# Payloadv03.net
KiCad netlist of a schematic drawn in EAGLE
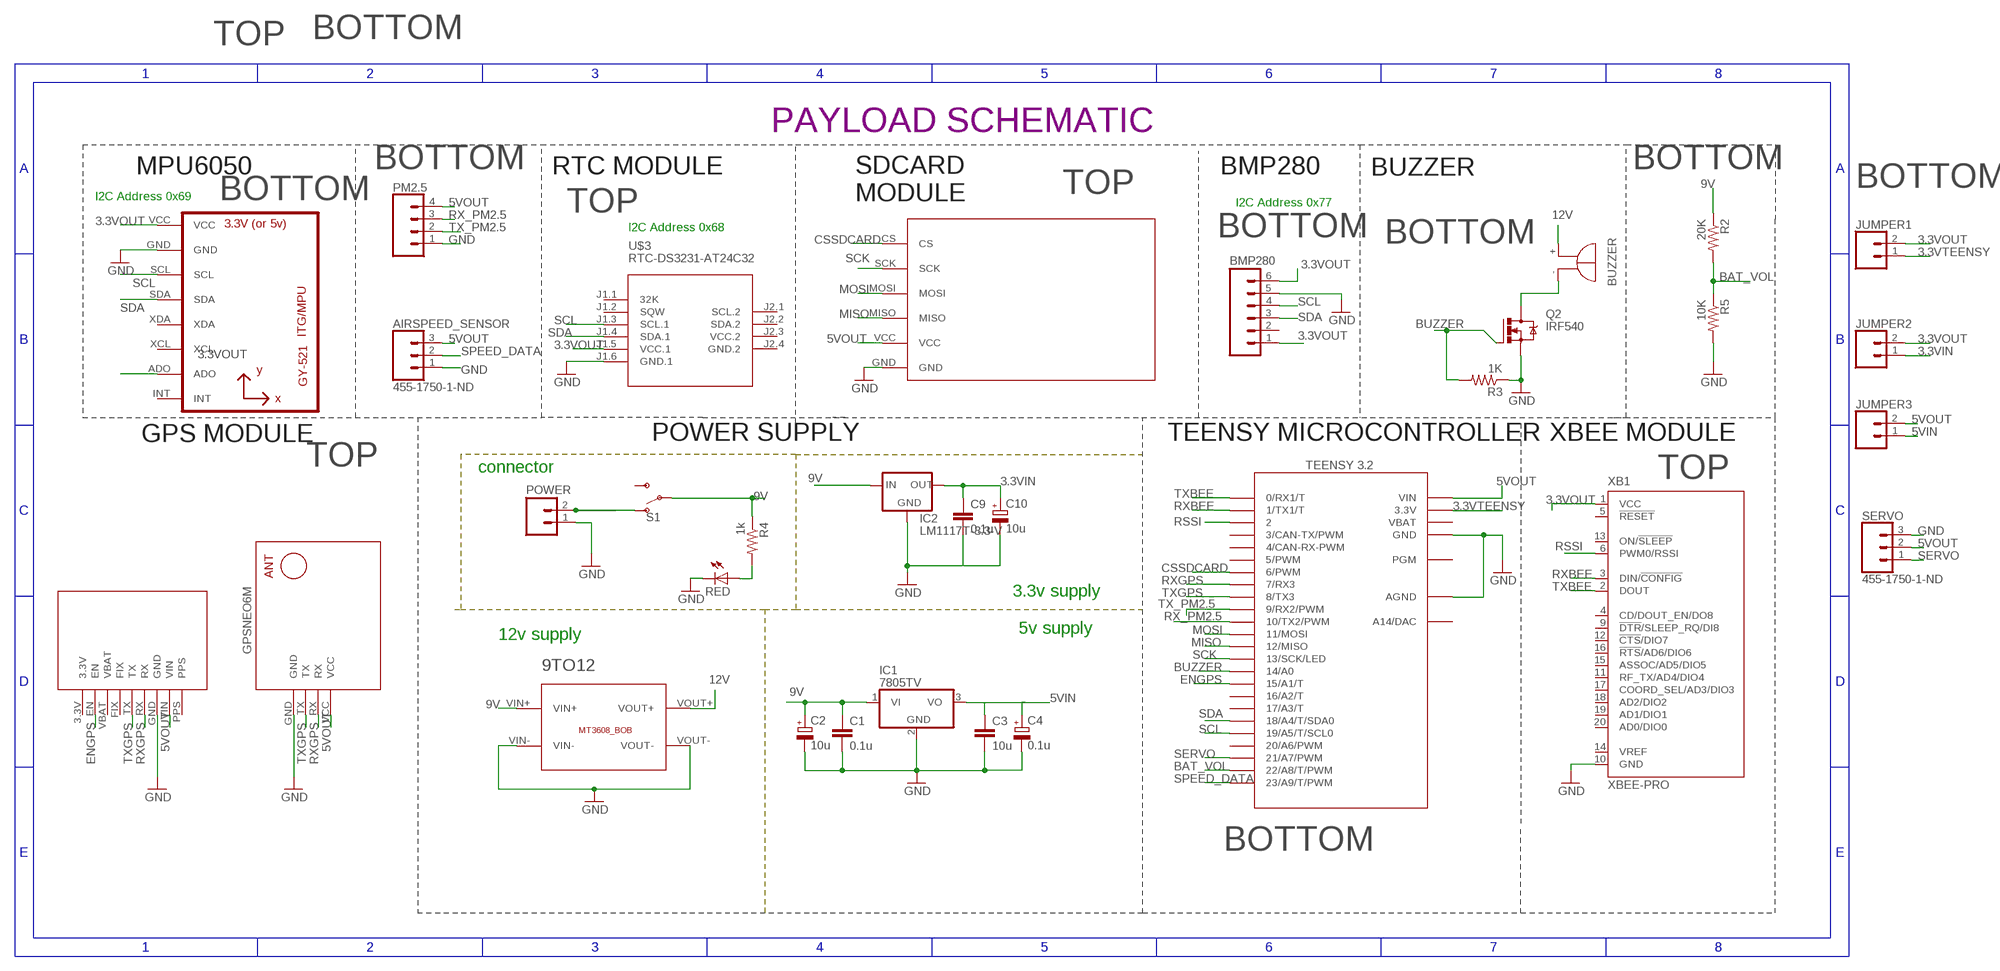
[diagram p0: schematic, sheet 1]

(export (version "E")
  (design (tool "Eeschema 10.0.6"))
  (components
    (comp (ref "9TO12")
      (value "BREAKOUTS_MT3608_BOB")
      (footprint "eagle-import:BREAKOUTS_MT3608_BOB")
      (libsource (lib "eagle-import") (part "BREAKOUTS_MT3608_BOB"))
    )
    (comp (ref "AIRSPEED_SENSOR")
      (value "455-1750-1-ND")
      (footprint "eagle-import:1X03")
      (libsource (lib "eagle-import") (part "CONN_03"))
    )
    (comp (ref "BMP280")
      (value "M06")
      (footprint "eagle-import:06P")
      (libsource (lib "eagle-import") (part "M06"))
    )
    (comp (ref "C1")
      (value "0.1u")
      (footprint "eagle-import:C025-025X050")
      (libsource (lib "eagle-import") (part "C-EU025-025X050"))
    )
    (comp (ref "C2")
      (value "10u")
      (footprint "eagle-import:E2,5-6")
      (libsource (lib "eagle-import") (part "CPOL-EUE2.5-6"))
    )
    (comp (ref "C3")
      (value "10u")
      (footprint "eagle-import:C025-025X050")
      (libsource (lib "eagle-import") (part "C-EU025-025X050"))
    )
    (comp (ref "C4")
      (value "0.1u")
      (footprint "eagle-import:E2,5-6")
      (libsource (lib "eagle-import") (part "CPOL-EUE2.5-6"))
    )
    (comp (ref "C9")
      (value "0.1u")
      (footprint "eagle-import:C025-025X050")
      (libsource (lib "eagle-import") (part "C-EU025-025X050"))
    )
    (comp (ref "C10")
      (value "10u")
      (footprint "eagle-import:E2,5-6")
      (libsource (lib "eagle-import") (part "CPOL-EUE2.5-6"))
    )
    (comp (ref "IC1")
      (value "7805TV")
      (footprint "eagle-import:TO220V")
      (libsource (lib "eagle-import") (part "78TV05"))
    )
    (comp (ref "IC2")
      (value "LM1117T-3.3-V")
      (footprint "eagle-import:TO220V")
      (libsource (lib "eagle-import") (part "LM1117T--V3.3"))
    )
    (comp (ref "JUMPER1")
      (value "CONN_02")
      (footprint "eagle-import:1X02")
      (libsource (lib "eagle-import") (part "CONN_02"))
    )
    (comp (ref "JUMPER2")
      (value "CONN_02")
      (footprint "eagle-import:1X02")
      (libsource (lib "eagle-import") (part "CONN_02"))
    )
    (comp (ref "JUMPER3")
      (value "CONN_02")
      (footprint "eagle-import:1X02")
      (libsource (lib "eagle-import") (part "CONN_02"))
    )
    (comp (ref "PM2.5")
      (value "CONN_04")
      (footprint "eagle-import:1X04")
      (libsource (lib "eagle-import") (part "CONN_04"))
    )
    (comp (ref "POWER")
      (value "CEDT_JANUARY_2015_V5_M02")
      (footprint "eagle-import:CEDT_JANUARY_2015_V5_02P")
      (libsource (lib "eagle-import") (part "CEDT_JANUARY_2015_V5_M02"))
    )
    (comp (ref "Q2")
      (value "IRF540")
      (footprint "eagle-import:TO220BV")
      (libsource (lib "eagle-import") (part "IRF540"))
    )
    (comp (ref "R2")
      (value "20K")
      (footprint "eagle-import:0204_7")
      (libsource (lib "eagle-import") (part "R-US_0204/7"))
    )
    (comp (ref "R3")
      (value "1K")
      (footprint "eagle-import:0204_7")
      (libsource (lib "eagle-import") (part "R-US_0204/7"))
    )
    (comp (ref "R4")
      (value "1k")
      (footprint "eagle-import:0204_7")
      (libsource (lib "eagle-import") (part "R-US_0204/7"))
    )
    (comp (ref "R5")
      (value "10K")
      (footprint "eagle-import:0204_7")
      (libsource (lib "eagle-import") (part "R-US_0204/7"))
    )
    (comp (ref "RED")
      (value "red")
      (footprint "eagle-import:LED3MM")
      (libsource (lib "eagle-import") (part "LED3MM"))
    )
    (comp (ref "S1")
      (value "SWITCH-SPDT-PTH-11.6X4.0MM")
      (footprint "eagle-import:SWITCH_SPDT_PTH_11.6X4.0MM")
      (libsource (lib "eagle-import") (part "SWITCH-SPDT-PTH-11.6X4.0MM"))
    )
    (comp (ref "SERVO")
      (value "455-1750-1-ND")
      (footprint "eagle-import:1X03")
      (libsource (lib "eagle-import") (part "CONN_03"))
    )
    (comp (ref "SG1")
      (value "BUZZER_EB2209A")
      (footprint "eagle-import:BUZZER_EB2209A")
      (libsource (lib "eagle-import") (part "BUZZER_EB2209A"))
    )
    (comp (ref "U$1")
      (value "GPS-RECEIVER-NEO6M")
      (footprint "eagle-import:GPS-RECEIVER-NEO6M")
      (libsource (lib "eagle-import") (part "GPS-RECEIVER-NEO6M"))
    )
    (comp (ref "U$2")
      (value "TEENSY_3.1-3.2_OUTER_ROW")
      (footprint "eagle-import:TEENSY_3.0-3.2&LC_OUTER_ROW")
      (libsource (lib "eagle-import") (part "TEENSY_3.1-3.2_OUTER_ROW"))
    )
    (comp (ref "U$3")
      (value "RTC-DS3231-AT24C32")
      (footprint "eagle-import:RTC-DS3231-AT24C32")
      (libsource (lib "eagle-import") (part "RTC-DS3231-AT24C32"))
    )
    (comp (ref "U$4")
      (value "ADAFRUIT_GPS")
      (footprint "eagle-import:ADAFRUIT_GPS")
      (libsource (lib "eagle-import") (part "ADAFRUIT_GPS"))
    )
    (comp (ref "U$5")
      (value "SDCARD")
      (footprint "eagle-import:M0SDCARDMODULE")
      (libsource (lib "eagle-import") (part "SDCARD"))
    )
    (comp (ref "U1")
      (value "GY-521MPU6050")
      (footprint "eagle-import:GY-521")
      (libsource (lib "eagle-import") (part "GY-521MPU6050"))
    )
    (comp (ref "XB1")
      (value "XBEE-PRO")
      (footprint "eagle-import:XBEE-PRO")
      (fields (field (name "MPN") "XBP24-AWI-001"))
      (libsource (lib "eagle-import") (part "XBEE-PRO"))
    )
  )
  (nets
    (net (code "1") (name "/3.3VIN") (class "Default")
      (node (ref "C10") (pin "+") (pinfunction "+_+") (pintype "passive"))
      (node (ref "C9") (pin "1") (pinfunction "1_1") (pintype "passive"))
      (node (ref "IC2") (pin "2") (pinfunction "OUT_2") (pintype "passive"))
      (node (ref "JUMPER2") (pin "1") (pinfunction "1_1") (pintype "passive"))
    )
    (net (code "2") (name "/3.3VOUT") (class "Default")
      (node (ref "BMP280") (pin "1") (pinfunction "1_1") (pintype "passive"))
      (node (ref "BMP280") (pin "6") (pinfunction "6_6") (pintype "passive"))
      (node (ref "JUMPER1") (pin "2") (pinfunction "2_2") (pintype "passive"))
      (node (ref "JUMPER2") (pin "2") (pinfunction "2_2") (pintype "passive"))
      (node (ref "U$3") (pin "J1.5") (pinfunction "VCC.1_J1.5") (pintype "power_in"))
      (node (ref "U1") (pin "ADO") (pinfunction "ADO_ADO") (pintype "bidirectional"))
      (node (ref "U1") (pin "VCC") (pinfunction "VCC_VCC") (pintype "bidirectional"))
      (node (ref "XB1") (pin "1") (pinfunction "VCC_1") (pintype "power_in"))
    )
    (net (code "3") (name "/3.3VTEENSY") (class "Default")
      (node (ref "JUMPER1") (pin "1") (pinfunction "1_1") (pintype "passive"))
      (node (ref "U$2") (pin "3.3V") (pinfunction "3.3V_3.3V") (pintype "power_in"))
      (node (ref "U$2") (pin "3.3V1") (pinfunction "3.3V_3.3V1") (pintype "power_in"))
    )
    (net (code "4") (name "/5VIN") (class "Default")
      (node (ref "C3") (pin "1") (pinfunction "1_1") (pintype "passive"))
      (node (ref "C4") (pin "+") (pinfunction "+_+") (pintype "passive"))
      (node (ref "IC1") (pin "3") (pinfunction "VO_3") (pintype "passive"))
      (node (ref "JUMPER3") (pin "1") (pinfunction "1_1") (pintype "passive"))
    )
    (net (code "5") (name "/5VOUT") (class "Default")
      (node (ref "AIRSPEED_SENSOR") (pin "3") (pinfunction "3_3") (pintype "passive"))
      (node (ref "JUMPER3") (pin "2") (pinfunction "2_2") (pintype "passive"))
      (node (ref "PM2.5") (pin "4") (pinfunction "4_4") (pintype "passive"))
      (node (ref "SERVO") (pin "2") (pinfunction "2_2") (pintype "passive"))
      (node (ref "U$1") (pin "VCC") (pinfunction "VCC_VCC") (pintype "power_in"))
      (node (ref "U$2") (pin "VIN") (pinfunction "VIN_VIN") (pintype "power_in"))
      (node (ref "U$4") (pin "VIN") (pinfunction "VIN_VIN") (pintype "bidirectional"))
      (node (ref "U$5") (pin "VCC") (pinfunction "VCC_VCC") (pintype "bidirectional"))
    )
    (net (code "6") (name "/9V") (class "Default")
      (node (ref "9TO12") (pin "VIN+") (pinfunction "VIN+_VIN+") (pintype "bidirectional"))
      (node (ref "C1") (pin "1") (pinfunction "1_1") (pintype "passive"))
      (node (ref "C2") (pin "+") (pinfunction "+_+") (pintype "passive"))
      (node (ref "IC1") (pin "1") (pinfunction "VI_1") (pintype "input"))
      (node (ref "IC2") (pin "3") (pinfunction "IN_3") (pintype "input"))
      (node (ref "R2") (pin "1") (pinfunction "1_1") (pintype "passive"))
      (node (ref "R4") (pin "1") (pinfunction "1_1") (pintype "passive"))
      (node (ref "S1") (pin "2") (pinfunction "P_2") (pintype "passive"))
    )
    (net (code "7") (name "/12V") (class "Default")
      (node (ref "9TO12") (pin "VOUT+") (pinfunction "VOUT+_VOUT+") (pintype "bidirectional"))
      (node (ref "SG1") (pin "+") (pinfunction "+_+") (pintype "passive"))
    )
    (net (code "8") (name "/BAT_VOL") (class "Default")
      (node (ref "R2") (pin "2") (pinfunction "2_2") (pintype "passive"))
      (node (ref "R5") (pin "1") (pinfunction "1_1") (pintype "passive"))
      (node (ref "U$2") (pin "22/A8") (pinfunction "22/A8/T/PWM_22/A8") (pintype "bidirectional"))
    )
    (net (code "9") (name "/BUZZER") (class "Default")
      (node (ref "Q2") (pin "G") (pinfunction "G_G") (pintype "passive"))
      (node (ref "R3") (pin "2") (pinfunction "2_2") (pintype "passive"))
      (node (ref "U$2") (pin "14/A0") (pinfunction "14/A0_14/A0") (pintype "bidirectional"))
    )
    (net (code "10") (name "/CSSDCARD") (class "Default")
      (node (ref "U$2") (pin "6") (pinfunction "6/PWM_6") (pintype "bidirectional"))
      (node (ref "U$5") (pin "CS") (pinfunction "CS_CS") (pintype "bidirectional"))
    )
    (net (code "11") (name "/ENGPS") (class "Default")
      (node (ref "U$2") (pin "15/A1") (pinfunction "15/A1/T_15/A1") (pintype "bidirectional"))
      (node (ref "U$4") (pin "EN") (pinfunction "EN_EN") (pintype "bidirectional"))
    )
    (net (code "12") (name "/GND.2") (class "Default")
      (node (ref "U$3") (pin "J2.4") (pinfunction "GND.2_J2.4") (pintype "power_in"))
    )
    (net (code "13") (name "/MISO") (class "Default")
      (node (ref "U$2") (pin "12") (pinfunction "12/MISO_12") (pintype "bidirectional"))
      (node (ref "U$5") (pin "MISO") (pinfunction "MISO_MISO") (pintype "bidirectional"))
    )
    (net (code "14") (name "/MOSI") (class "Default")
      (node (ref "U$2") (pin "11") (pinfunction "11/MOSI_11") (pintype "bidirectional"))
      (node (ref "U$5") (pin "MOSI") (pinfunction "MOSI_MOSI") (pintype "bidirectional"))
    )
    (net (code "15") (name "/RSSI") (class "Default")
      (node (ref "U$2") (pin "2") (pinfunction "2_2") (pintype "bidirectional"))
      (node (ref "XB1") (pin "6") (pinfunction "PWM0/RSSI_6") (pintype "output"))
    )
    (net (code "16") (name "/RXBEE") (class "Default")
      (node (ref "U$2") (pin "1") (pinfunction "1/TX1/T_1") (pintype "bidirectional"))
      (node (ref "XB1") (pin "3") (pinfunction "DIN/~{CONFIG}_3") (pintype "input"))
    )
    (net (code "17") (name "/RXGPS") (class "Default")
      (node (ref "U$1") (pin "RX") (pinfunction "RX_RX") (pintype "bidirectional"))
      (node (ref "U$2") (pin "7") (pinfunction "7/RX3_7") (pintype "bidirectional"))
      (node (ref "U$4") (pin "RX") (pinfunction "RX_RX") (pintype "bidirectional"))
    )
    (net (code "18") (name "/RX_PM2.5") (class "Default")
      (node (ref "PM2.5") (pin "3") (pinfunction "3_3") (pintype "passive"))
      (node (ref "U$2") (pin "10") (pinfunction "10/TX2/PWM_10") (pintype "bidirectional"))
    )
    (net (code "19") (name "/SCK") (class "Default")
      (node (ref "U$2") (pin "13") (pinfunction "13/SCK/LED_13") (pintype "bidirectional"))
      (node (ref "U$5") (pin "SCK") (pinfunction "SCK_SCK") (pintype "bidirectional"))
    )
    (net (code "20") (name "/SCL") (class "Default")
      (node (ref "BMP280") (pin "4") (pinfunction "4_4") (pintype "passive"))
      (node (ref "U$2") (pin "19/A5") (pinfunction "19/A5/T/SCL0_19/A5") (pintype "bidirectional"))
      (node (ref "U$3") (pin "J1.3") (pinfunction "SCL.1_J1.3") (pintype "bidirectional"))
      (node (ref "U1") (pin "SCL") (pinfunction "SCL_SCL") (pintype "bidirectional"))
    )
    (net (code "21") (name "/SDA") (class "Default")
      (node (ref "BMP280") (pin "3") (pinfunction "3_3") (pintype "passive"))
      (node (ref "U$2") (pin "18/A4") (pinfunction "18/A4/T/SDA0_18/A4") (pintype "bidirectional"))
      (node (ref "U$3") (pin "J1.4") (pinfunction "SDA.1_J1.4") (pintype "bidirectional"))
      (node (ref "U1") (pin "SDA") (pinfunction "SDA_SDA") (pintype "bidirectional"))
    )
    (net (code "22") (name "/SERVO") (class "Default")
      (node (ref "SERVO") (pin "1") (pinfunction "1_1") (pintype "passive"))
      (node (ref "U$2") (pin "21/A7") (pinfunction "21/A7/PWM_21/A7") (pintype "bidirectional"))
    )
    (net (code "23") (name "/SPEED_DATA") (class "Default")
      (node (ref "AIRSPEED_SENSOR") (pin "2") (pinfunction "2_2") (pintype "passive"))
      (node (ref "U$2") (pin "23/A9") (pinfunction "23/A9/T/PWM_23/A9") (pintype "bidirectional"))
    )
    (net (code "24") (name "/TXBEE") (class "Default")
      (node (ref "U$2") (pin "0") (pinfunction "0/RX1/T_0") (pintype "bidirectional"))
      (node (ref "XB1") (pin "2") (pinfunction "DOUT_2") (pintype "output"))
    )
    (net (code "25") (name "/TXGPS") (class "Default")
      (node (ref "U$1") (pin "TX") (pinfunction "TX_TX") (pintype "bidirectional"))
      (node (ref "U$2") (pin "8") (pinfunction "8/TX3_8") (pintype "bidirectional"))
      (node (ref "U$4") (pin "TX") (pinfunction "TX_TX") (pintype "bidirectional"))
    )
    (net (code "26") (name "/TX_PM2.5") (class "Default")
      (node (ref "PM2.5") (pin "2") (pinfunction "2_2") (pintype "passive"))
      (node (ref "U$2") (pin "9") (pinfunction "9/RX2/PWM_9") (pintype "bidirectional"))
    )
    (net (code "27") (name "/VBAT") (class "Default")
      (node (ref "U$2") (pin "VBAT") (pinfunction "VBAT_VBAT") (pintype "power_in"))
    )
    (net (code "28") (name "/VCC.2") (class "Default")
      (node (ref "U$3") (pin "J2.3") (pinfunction "VCC.2_J2.3") (pintype "power_in"))
    )
    (net (code "29") (name "GND") (class "Default")
      (node (ref "9TO12") (pin "VIN-") (pinfunction "VIN-_VIN-") (pintype "bidirectional"))
      (node (ref "9TO12") (pin "VOUT-") (pinfunction "VOUT-_VOUT-") (pintype "bidirectional"))
      (node (ref "AIRSPEED_SENSOR") (pin "1") (pinfunction "1_1") (pintype "passive"))
      (node (ref "BMP280") (pin "5") (pinfunction "5_5") (pintype "passive"))
      (node (ref "C1") (pin "2") (pinfunction "2_2") (pintype "passive"))
      (node (ref "C10") (pin "-") (pinfunction "-_-") (pintype "passive"))
      (node (ref "C2") (pin "-") (pinfunction "-_-") (pintype "passive"))
      (node (ref "C3") (pin "2") (pinfunction "2_2") (pintype "passive"))
      (node (ref "C4") (pin "-") (pinfunction "-_-") (pintype "passive"))
      (node (ref "C9") (pin "2") (pinfunction "2_2") (pintype "passive"))
      (node (ref "IC1") (pin "2") (pinfunction "GND_2") (pintype "passive"))
      (node (ref "IC2") (pin "1") (pinfunction "GND_1") (pintype "input"))
      (node (ref "PM2.5") (pin "1") (pinfunction "1_1") (pintype "passive"))
      (node (ref "POWER") (pin "1") (pinfunction "1_1") (pintype "passive"))
      (node (ref "Q2") (pin "S") (pinfunction "S_S") (pintype "passive"))
      (node (ref "R3") (pin "1") (pinfunction "1_1") (pintype "passive"))
      (node (ref "R5") (pin "2") (pinfunction "2_2") (pintype "passive"))
      (node (ref "RED") (pin "K") (pinfunction "C_K") (pintype "passive"))
      (node (ref "SERVO") (pin "3") (pinfunction "3_3") (pintype "passive"))
      (node (ref "U$1") (pin "GND") (pinfunction "GND_GND") (pintype "bidirectional"))
      (node (ref "U$2") (pin "AGND") (pinfunction "AGND_AGND") (pintype "power_in"))
      (node (ref "U$2") (pin "GND") (pinfunction "GND_GND") (pintype "power_in"))
      (node (ref "U$2") (pin "GND1") (pinfunction "GND_GND1") (pintype "power_in"))
      (node (ref "U$3") (pin "J1.6") (pinfunction "GND.1_J1.6") (pintype "power_in"))
      (node (ref "U$4") (pin "GND") (pinfunction "GND_GND") (pintype "bidirectional"))
      (node (ref "U$5") (pin "GND") (pinfunction "GND_GND") (pintype "bidirectional"))
      (node (ref "U1") (pin "GND") (pinfunction "GND_GND") (pintype "bidirectional"))
      (node (ref "XB1") (pin "10") (pinfunction "GND_10") (pintype "power_in"))
    )
    (net (code "30") (name "Net-(Q2-PadD)") (class "Default")
      (node (ref "Q2") (pin "D") (pinfunction "D_D") (pintype "passive"))
      (node (ref "SG1") (pin "-") (pinfunction "-_-") (pintype "passive"))
    )
    (net (code "31") (name "Net-(R4-Pad2)") (class "Default")
      (node (ref "R4") (pin "2") (pinfunction "2_2") (pintype "passive"))
      (node (ref "RED") (pin "A") (pinfunction "A_A") (pintype "passive"))
    )
    (net (code "32") (name "Net-(S1-O)") (class "Default")
      (node (ref "POWER") (pin "2") (pinfunction "2_2") (pintype "passive"))
      (node (ref "S1") (pin "1") (pinfunction "O_1") (pintype "passive"))
    )
    (net (code "33") (name "unconnected-(BMP280-Pad2)") (class "Default")
      (node (ref "BMP280") (pin "2") (pinfunction "2_2") (pintype "passive"))
    )
    (net (code "34") (name "unconnected-(S1-S-Pad3)") (class "Default")
      (node (ref "S1") (pin "3") (pinfunction "S_3") (pintype "passive"))
    )
    (net (code "35") (name "unconnected-(U$2-3{slash}CAN-TX{slash}PWM-Pad3)") (class "Default")
      (node (ref "U$2") (pin "3") (pinfunction "3/CAN-TX/PWM_3") (pintype "bidirectional"))
    )
    (net (code "36") (name "unconnected-(U$2-4{slash}CAN-RX-PWM-Pad4)") (class "Default")
      (node (ref "U$2") (pin "4") (pinfunction "4/CAN-RX-PWM_4") (pintype "bidirectional"))
    )
    (net (code "37") (name "unconnected-(U$2-5{slash}PWM-Pad5)") (class "Default")
      (node (ref "U$2") (pin "5") (pinfunction "5/PWM_5") (pintype "bidirectional"))
    )
    (net (code "38") (name "unconnected-(U$2-16{slash}A2{slash}T-Pad16{slash}A2)") (class "Default")
      (node (ref "U$2") (pin "16/A2") (pinfunction "16/A2/T_16/A2") (pintype "bidirectional"))
    )
    (net (code "39") (name "unconnected-(U$2-17{slash}A3{slash}T-Pad17{slash}A3)") (class "Default")
      (node (ref "U$2") (pin "17/A3") (pinfunction "17/A3/T_17/A3") (pintype "bidirectional"))
    )
    (net (code "40") (name "unconnected-(U$2-20{slash}A6{slash}PWM-Pad20{slash}A6)") (class "Default")
      (node (ref "U$2") (pin "20/A6") (pinfunction "20/A6/PWM_20/A6") (pintype "bidirectional"))
    )
    (net (code "41") (name "unconnected-(U$2-A14{slash}DAC-PadRESET{slash}DAC)") (class "Default")
      (node (ref "U$2") (pin "RESET/DAC") (pinfunction "A14/DAC_RESET/DAC") (pintype "bidirectional"))
    )
    (net (code "42") (name "unconnected-(U$2-PadPGM)") (class "Default")
      (node (ref "U$2") (pin "PGM") (pinfunction "PGM_PGM") (pintype "bidirectional"))
    )
    (net (code "43") (name "unconnected-(U$3-32K-PadJ1.1)") (class "Default")
      (node (ref "U$3") (pin "J1.1") (pinfunction "32K_J1.1") (pintype "bidirectional"))
    )
    (net (code "44") (name "unconnected-(U$3-SCL.2-PadJ2.1)") (class "Default")
      (node (ref "U$3") (pin "J2.1") (pinfunction "SCL.2_J2.1") (pintype "bidirectional"))
    )
    (net (code "45") (name "unconnected-(U$3-SDA.2-PadJ2.2)") (class "Default")
      (node (ref "U$3") (pin "J2.2") (pinfunction "SDA.2_J2.2") (pintype "bidirectional"))
    )
    (net (code "46") (name "unconnected-(U$3-SQW-PadJ1.2)") (class "Default")
      (node (ref "U$3") (pin "J1.2") (pinfunction "SQW_J1.2") (pintype "bidirectional"))
    )
    (net (code "47") (name "unconnected-(U$4-Pad3.3V)") (class "Default")
      (node (ref "U$4") (pin "3.3V") (pinfunction "3.3V_3.3V") (pintype "bidirectional"))
    )
    (net (code "48") (name "unconnected-(U$4-PadFIX)") (class "Default")
      (node (ref "U$4") (pin "FIX") (pinfunction "FIX_FIX") (pintype "bidirectional"))
    )
    (net (code "49") (name "unconnected-(U$4-PadPPS)") (class "Default")
      (node (ref "U$4") (pin "PPS") (pinfunction "PPS_PPS") (pintype "bidirectional"))
    )
    (net (code "50") (name "unconnected-(U$4-PadVBAT)") (class "Default")
      (node (ref "U$4") (pin "VBAT") (pinfunction "VBAT_VBAT") (pintype "bidirectional"))
    )
    (net (code "51") (name "unconnected-(U1-PadINT)") (class "Default")
      (node (ref "U1") (pin "INT") (pinfunction "INT_INT") (pintype "bidirectional"))
    )
    (net (code "52") (name "unconnected-(U1-PadXCL)") (class "Default")
      (node (ref "U1") (pin "XCL") (pinfunction "XCL_XCL") (pintype "bidirectional"))
    )
    (net (code "53") (name "unconnected-(U1-PadXDA)") (class "Default")
      (node (ref "U1") (pin "XDA") (pinfunction "XDA_XDA") (pintype "bidirectional"))
    )
    (net (code "54") (name "unconnected-(XB1-AD0{slash}DIO0-Pad20)") (class "Default")
      (node (ref "XB1") (pin "20") (pinfunction "AD0/DIO0_20") (pintype "bidirectional"))
    )
    (net (code "55") (name "unconnected-(XB1-AD1{slash}DIO1-Pad19)") (class "Default")
      (node (ref "XB1") (pin "19") (pinfunction "AD1/DIO1_19") (pintype "bidirectional"))
    )
    (net (code "56") (name "unconnected-(XB1-AD2{slash}DIO2-Pad18)") (class "Default")
      (node (ref "XB1") (pin "18") (pinfunction "AD2/DIO2_18") (pintype "bidirectional"))
    )
    (net (code "57") (name "unconnected-(XB1-ASSOC{slash}AD5{slash}DIO5-Pad15)") (class "Default")
      (node (ref "XB1") (pin "15") (pinfunction "ASSOC/AD5/DIO5_15") (pintype "bidirectional"))
    )
    (net (code "58") (name "unconnected-(XB1-CD{slash}DOUT_EN{slash}DO8-Pad4)") (class "Default")
      (node (ref "XB1") (pin "4") (pinfunction "CD/DOUT_EN/DO8_4") (pintype "output"))
    )
    (net (code "59") (name "unconnected-(XB1-COORD_SEL{slash}AD3{slash}DIO3-Pad17)") (class "Default")
      (node (ref "XB1") (pin "17") (pinfunction "COORD_SEL/AD3/DIO3_17") (pintype "bidirectional"))
    )
    (net (code "60") (name "unconnected-(XB1-ON{slash}~{SLEEP}-Pad13)") (class "Default")
      (node (ref "XB1") (pin "13") (pinfunction "ON/~{SLEEP}_13") (pintype "output"))
    )
    (net (code "61") (name "unconnected-(XB1-RF_TX{slash}AD4{slash}DIO4-Pad11)") (class "Default")
      (node (ref "XB1") (pin "11") (pinfunction "RF_TX/AD4/DIO4_11") (pintype "bidirectional"))
    )
    (net (code "62") (name "unconnected-(XB1-VREF-Pad14)") (class "Default")
      (node (ref "XB1") (pin "14") (pinfunction "VREF_14") (pintype "input"))
    )
    (net (code "63") (name "unconnected-(XB1-~{CTS}{slash}DIO7-Pad12)") (class "Default")
      (node (ref "XB1") (pin "12") (pinfunction "~{CTS}/DIO7_12") (pintype "bidirectional"))
    )
    (net (code "64") (name "unconnected-(XB1-~{DTR}{slash}SLEEP_RQ{slash}DI8-Pad9)") (class "Default")
      (node (ref "XB1") (pin "9") (pinfunction "~{DTR}/SLEEP_RQ/DI8_9") (pintype "bidirectional"))
    )
    (net (code "65") (name "unconnected-(XB1-~{RESET}-Pad5)") (class "Default")
      (node (ref "XB1") (pin "5") (pinfunction "~{RESET}_5") (pintype "input"))
    )
    (net (code "66") (name "unconnected-(XB1-~{RTS}{slash}AD6{slash}DIO6-Pad16)") (class "Default")
      (node (ref "XB1") (pin "16") (pinfunction "~{RTS}/AD6/DIO6_16") (pintype "bidirectional"))
    )
  )
)
